# SCH_Dashboy_camera_NiMH_2023-03-29.net
KiCad netlist of a schematic drawn in EasyEDA
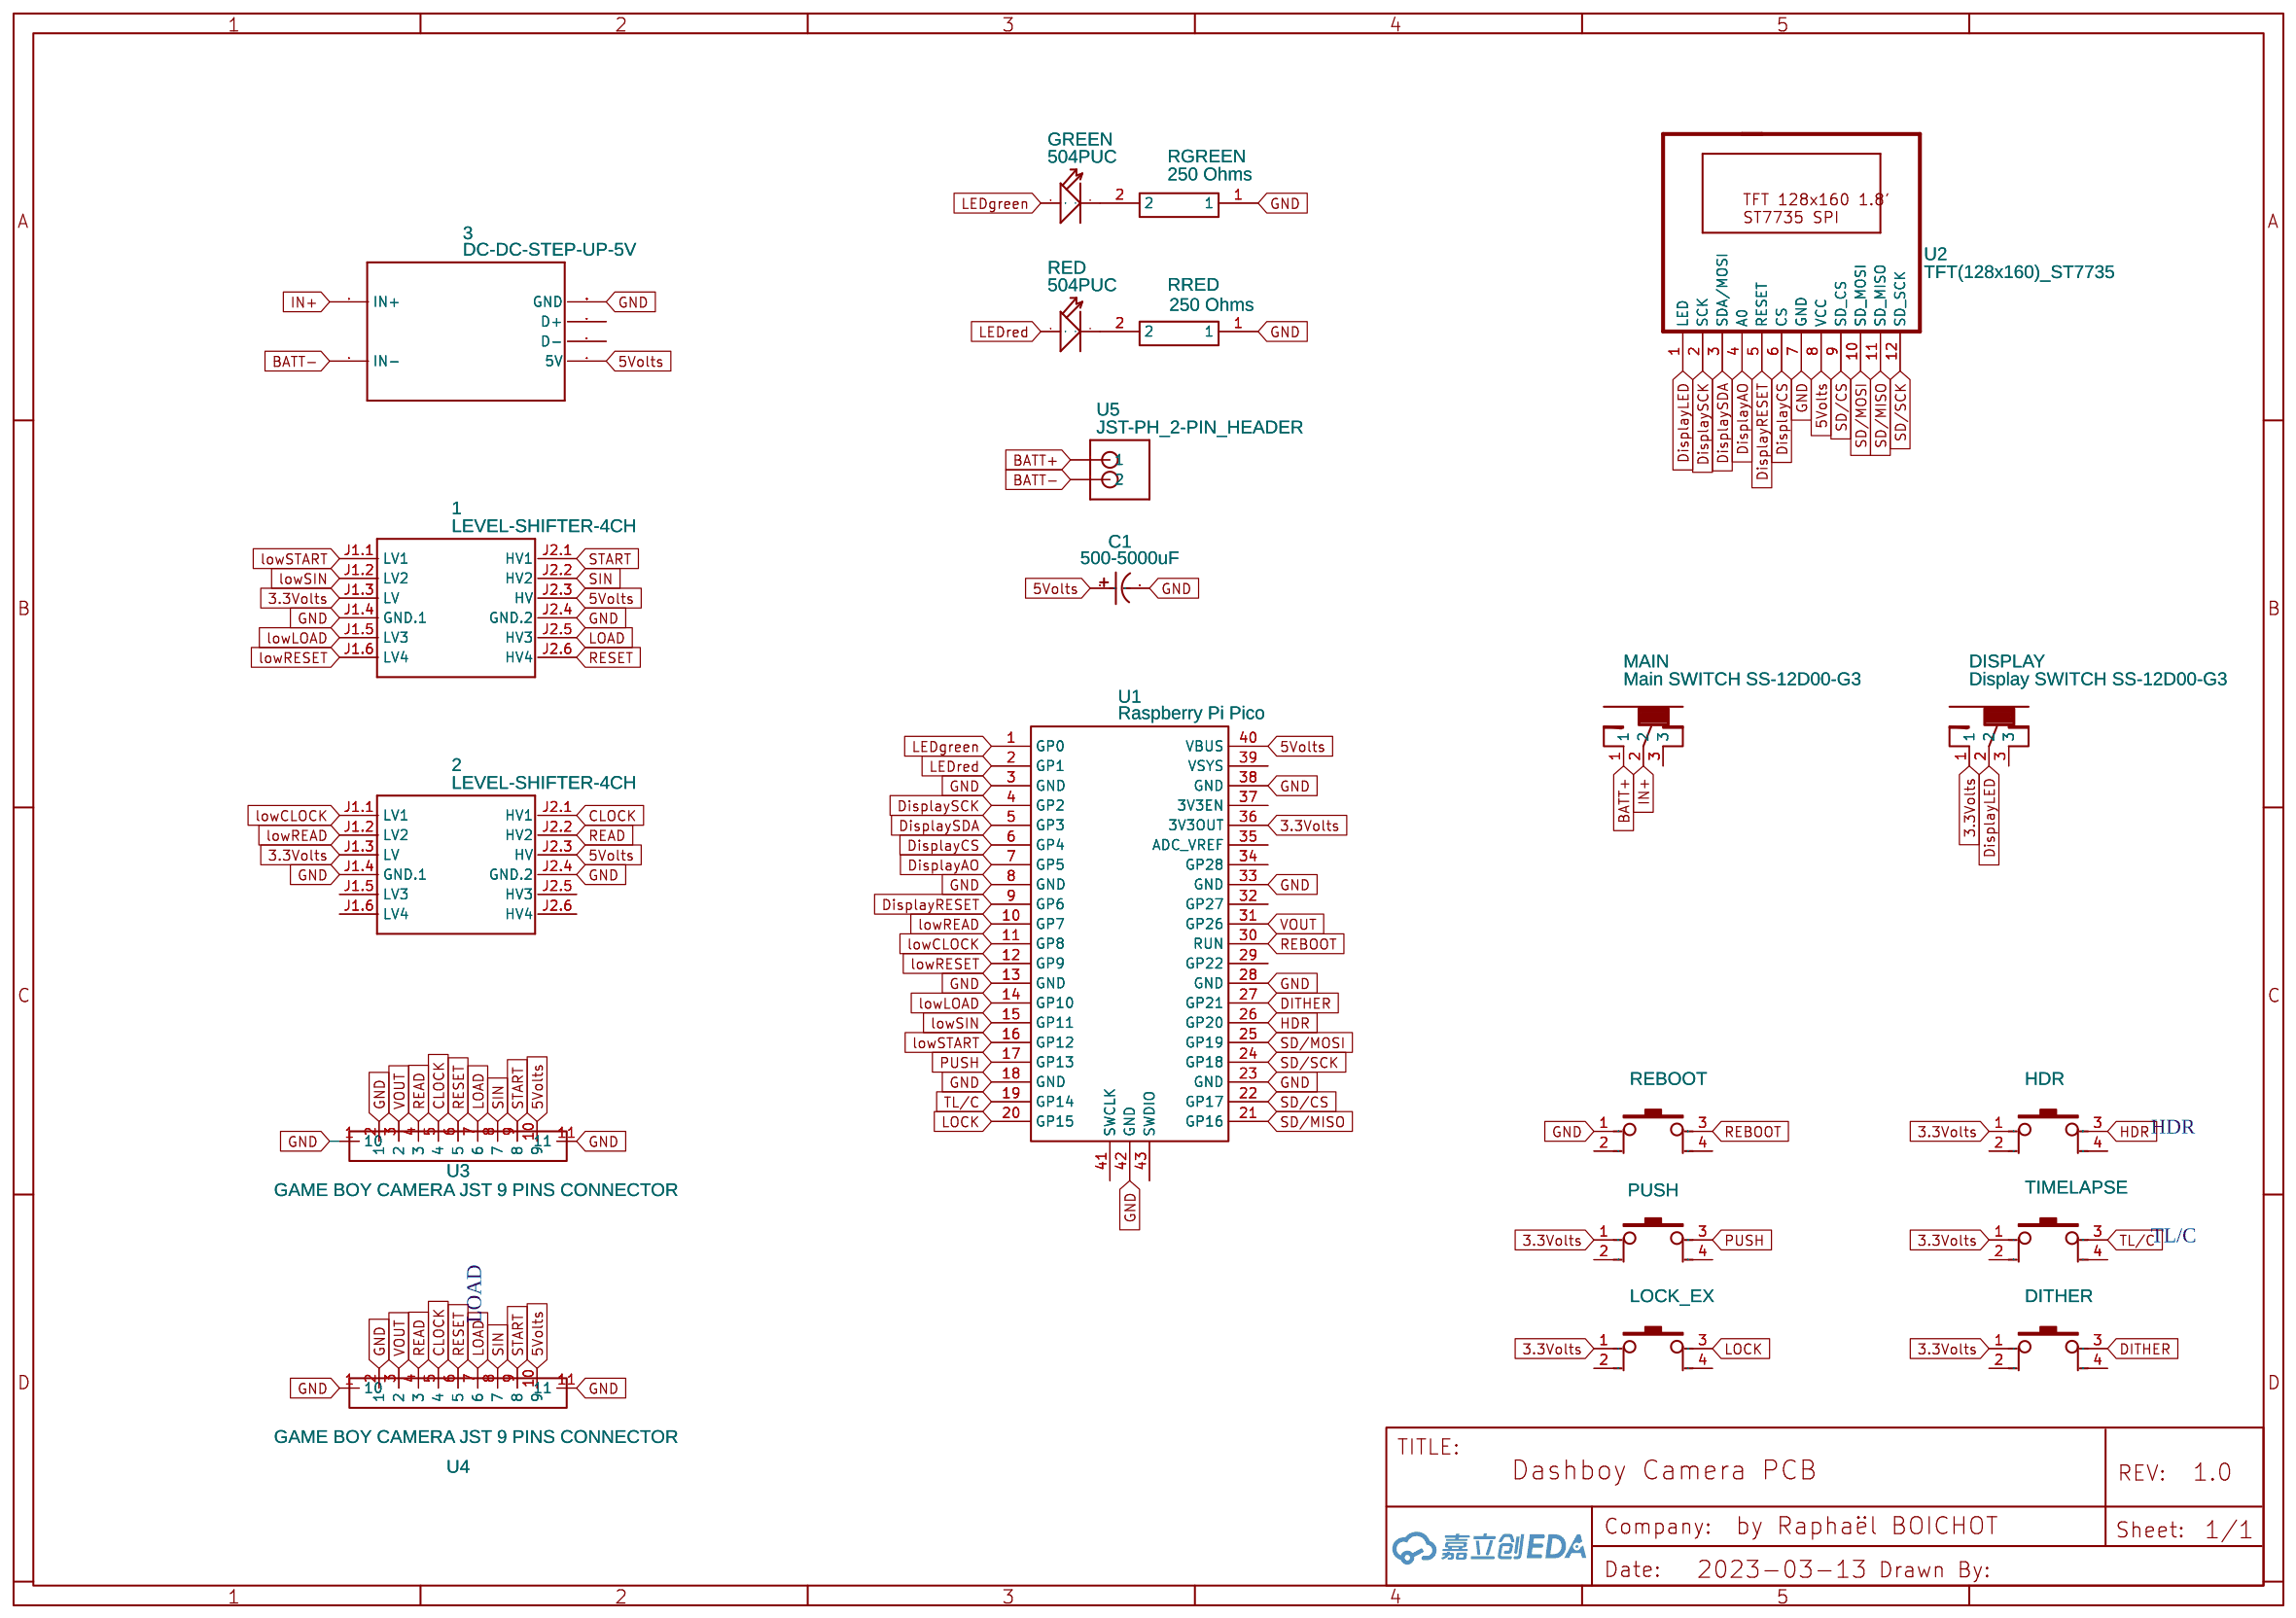
[diagram p0: schematic sheet]

(export (version "E")
  (design (tool "Eeschema 10.0.6"))
  (components
    (comp (ref "1") (value "LEVEL-SHIFTER-4CH") (libsource (lib "") (part "LEVEL-SHIFTER-4CH")))
    (comp (ref "2") (value "LEVEL-SHIFTER-4CH") (libsource (lib "") (part "LEVEL-SHIFTER-4CH")))
    (comp (ref "3") (value "DC-DC-STEP-UP-5V") (libsource (lib "") (part "DC-DC-STEP-UP-5V")))
    (comp (ref "C1")
      (value "500-5000uF")
      (fields
        (field (name "BOM_Manufacturer Part") "GR106M050D11RR0VK2FP0")
        (field (name "BOM_Supplier Part") "C78759")
      )
      (libsource (lib "") (part "electrolytic capacitor 10UF 50V high frequency"))
    )
    (comp (ref "DISPLAY")
      (value "Display SWITCH SS-12D00-G3")
      (fields (field (name "BOM_Manufacturer Part") "TOGGLE SWITCH SS-12D00-G3"))
      (libsource (lib "") (part "TOGGLE SWITCH SS-12D00-G3"))
    )
    (comp (ref "DITHER")
      (value "BoutonPoussoir")
      (fields
        (field (name "BOM_Manufacturer Part") "button6*6*8")
        (field (name "BOM_Supplier Part") "C59982")
      )
      (libsource (lib "") (part "BoutonPoussoir_1"))
    )
    (comp (ref "GREEN") (value "504PUC") (libsource (lib "") (part "504PUC")))
    (comp (ref "HDR")
      (value "BoutonPoussoir")
      (fields
        (field (name "BOM_Manufacturer Part") "button6*6*8")
        (field (name "BOM_Supplier Part") "C59982")
      )
      (libsource (lib "") (part "BoutonPoussoir_2"))
    )
    (comp (ref "LOCK_EX")
      (value "BoutonPoussoir")
      (fields
        (field (name "BOM_Manufacturer Part") "button6*6*8")
        (field (name "BOM_Supplier Part") "C59982")
      )
      (libsource (lib "") (part "BoutonPoussoir_5"))
    )
    (comp (ref "MAIN")
      (value "Main SWITCH SS-12D00-G3")
      (fields (field (name "BOM_Manufacturer Part") "TOGGLE SWITCH SS-12D00-G3"))
      (libsource (lib "") (part "TOGGLE SWITCH SS-12D00-G3_1"))
    )
    (comp (ref "PUSH")
      (value "BoutonPoussoir")
      (fields
        (field (name "BOM_Manufacturer Part") "button6*6*8")
        (field (name "BOM_Supplier Part") "C59982")
      )
      (libsource (lib "") (part "BoutonPoussoir_4"))
    )
    (comp (ref "REBOOT")
      (value "BoutonPoussoir")
      (fields
        (field (name "BOM_Manufacturer Part") "button6*6*8")
        (field (name "BOM_Supplier Part") "C59982")
      )
      (libsource (lib "") (part "BoutonPoussoir"))
    )
    (comp (ref "RED") (value "504PUC") (libsource (lib "") (part "504PUC_1")))
    (comp (ref "RGREEN") (value "250 Ohms") (libsource (lib "") (part "RESITOR")))
    (comp (ref "RRED") (value "250 Ohms") (libsource (lib "") (part "RESITOR_1")))
    (comp (ref "TIMELAPSE")
      (value "BoutonPoussoir")
      (fields
        (field (name "BOM_Manufacturer Part") "button6*6*8")
        (field (name "BOM_Supplier Part") "C59982")
      )
      (libsource (lib "") (part "BoutonPoussoir_3"))
    )
    (comp (ref "U1") (value "Raspberry Pi Pico") (libsource (lib "") (part "Raspberry Pi Pico")))
    (comp (ref "U2") (value "TFT(128x160)_ST7735") (libsource (lib "") (part "TFT(128x160)_ST7735")))
    (comp (ref "U3")
      (value "GAME BOY CAMERA JST 9 PINS CONNECTOR")
      (libsource (lib "") (part "GAME BOY CAMERA JST 9 PINS CONNECTOR"))
    )
    (comp (ref "U4")
      (value "GAME BOY CAMERA JST 9 PINS CONNECTOR")
      (libsource (lib "") (part "GAME BOY CAMERA JST 9 PINS CONNECTOR"))
    )
    (comp (ref "U5") (value "JST-PH_2-PIN_HEADER") (libsource (lib "") (part "JST-PH_2-PIN_HEADER")))
  )
  (nets
    (net (code "1") (name "3.3Volts") (class "Default")
      (node (ref "1") (pin "J1.3") (pinfunction "LV_J1.3") (pintype "bidirectional"))
      (node (ref "2") (pin "J1.3") (pinfunction "LV_J1.3") (pintype "bidirectional"))
      (node (ref "DISPLAY") (pin "1") (pinfunction "1_1") (pintype "bidirectional"))
      (node (ref "DITHER") (pin "1") (pinfunction "1_1") (pintype "input"))
      (node (ref "HDR") (pin "1") (pinfunction "1_1") (pintype "input"))
      (node (ref "LOCK_EX") (pin "1") (pinfunction "1_1") (pintype "input"))
      (node (ref "PUSH") (pin "1") (pinfunction "1_1") (pintype "input"))
      (node (ref "TIMELAPSE") (pin "1") (pinfunction "1_1") (pintype "input"))
      (node (ref "U1") (pin "36") (pinfunction "3V3OUT_36") (pintype "unspecified"))
    )
    (net (code "2") (name "5Volts") (class "Default")
      (node (ref "1") (pin "J2.3") (pinfunction "HV_J2.3") (pintype "bidirectional"))
      (node (ref "2") (pin "J2.3") (pinfunction "HV_J2.3") (pintype "bidirectional"))
      (node (ref "3") (pin "5V") (pinfunction "5V_5V") (pintype "bidirectional"))
      (node (ref "C1") (pin "1") (pinfunction "1_1") (pintype "input"))
      (node (ref "U1") (pin "40") (pinfunction "VBUS_40") (pintype "unspecified"))
      (node (ref "U2") (pin "8") (pinfunction "VCC_8") (pintype "input"))
      (node (ref "U3") (pin "10") (pinfunction "9_10") (pintype "unspecified"))
      (node (ref "U4") (pin "10") (pinfunction "9_10") (pintype "unspecified"))
    )
    (net (code "3") (name "BATT+") (class "Default")
      (node (ref "MAIN") (pin "1") (pinfunction "1_1") (pintype "bidirectional"))
      (node (ref "U5") (pin "P1") (pinfunction "1_P1") (pintype "unspecified"))
    )
    (net (code "4") (name "BATT-") (class "Default")
      (node (ref "3") (pin "IN-") (pinfunction "IN-_IN-") (pintype "bidirectional"))
      (node (ref "U5") (pin "P2") (pinfunction "2_P2") (pintype "unspecified"))
    )
    (net (code "5") (name "CLOCK") (class "Default")
      (node (ref "2") (pin "J2.1") (pinfunction "HV1_J2.1") (pintype "bidirectional"))
      (node (ref "U3") (pin "5") (pinfunction "4_5") (pintype "unspecified"))
      (node (ref "U4") (pin "5") (pinfunction "4_5") (pintype "unspecified"))
    )
    (net (code "6") (name "DITHER") (class "Default")
      (node (ref "DITHER") (pin "3") (pinfunction "3_3") (pintype "input"))
      (node (ref "U1") (pin "27") (pinfunction "GP21_27") (pintype "unspecified"))
    )
    (net (code "7") (name "DisplayAO") (class "Default")
      (node (ref "U1") (pin "7") (pinfunction "GP5_7") (pintype "unspecified"))
      (node (ref "U2") (pin "4") (pinfunction "A0_4") (pintype "input"))
    )
    (net (code "8") (name "DisplayCS") (class "Default")
      (node (ref "U1") (pin "6") (pinfunction "GP4_6") (pintype "unspecified"))
      (node (ref "U2") (pin "6") (pinfunction "CS_6") (pintype "input"))
    )
    (net (code "9") (name "DisplayLED") (class "Default")
      (node (ref "DISPLAY") (pin "2") (pinfunction "2_2") (pintype "bidirectional"))
      (node (ref "U2") (pin "1") (pinfunction "LED_1") (pintype "passive"))
    )
    (net (code "10") (name "DisplayRESET") (class "Default")
      (node (ref "U1") (pin "9") (pinfunction "GP6_9") (pintype "unspecified"))
      (node (ref "U2") (pin "5") (pinfunction "RESET_5") (pintype "input"))
    )
    (net (code "11") (name "DisplaySCK") (class "Default")
      (node (ref "U1") (pin "4") (pinfunction "GP2_4") (pintype "unspecified"))
      (node (ref "U2") (pin "2") (pinfunction "SCK_2") (pintype "output"))
    )
    (net (code "12") (name "DisplaySDA") (class "Default")
      (node (ref "U1") (pin "5") (pinfunction "GP3_5") (pintype "unspecified"))
      (node (ref "U2") (pin "3") (pinfunction "SDA/MOSI_3") (pintype "input"))
    )
    (net (code "13") (name "GND") (class "Default")
      (node (ref "1") (pin "J1.4") (pinfunction "GND.1_J1.4") (pintype "bidirectional"))
      (node (ref "1") (pin "J2.4") (pinfunction "GND.2_J2.4") (pintype "bidirectional"))
      (node (ref "2") (pin "J1.4") (pinfunction "GND.1_J1.4") (pintype "bidirectional"))
      (node (ref "2") (pin "J2.4") (pinfunction "GND.2_J2.4") (pintype "bidirectional"))
      (node (ref "3") (pin "GND") (pinfunction "GND_GND") (pintype "bidirectional"))
      (node (ref "C1") (pin "2") (pinfunction "2_2") (pintype "input"))
      (node (ref "REBOOT") (pin "1") (pinfunction "1_1") (pintype "input"))
      (node (ref "RGREEN") (pin "1") (pinfunction "1_1") (pintype "unspecified"))
      (node (ref "RRED") (pin "1") (pinfunction "1_1") (pintype "unspecified"))
      (node (ref "U1") (pin "13") (pinfunction "GND_13") (pintype "unspecified"))
      (node (ref "U1") (pin "18") (pinfunction "GND_18") (pintype "unspecified"))
      (node (ref "U1") (pin "23") (pinfunction "GND_23") (pintype "unspecified"))
      (node (ref "U1") (pin "28") (pinfunction "GND_28") (pintype "unspecified"))
      (node (ref "U1") (pin "3") (pinfunction "GND_3") (pintype "unspecified"))
      (node (ref "U1") (pin "33") (pinfunction "GND_33") (pintype "unspecified"))
      (node (ref "U1") (pin "38") (pinfunction "GND_38") (pintype "unspecified"))
      (node (ref "U1") (pin "42") (pinfunction "GND_42") (pintype "unspecified"))
      (node (ref "U1") (pin "8") (pinfunction "GND_8") (pintype "unspecified"))
      (node (ref "U2") (pin "7") (pinfunction "GND_7") (pintype "unspecified"))
      (node (ref "U3") (pin "1") (pinfunction "10_1") (pintype "unspecified"))
      (node (ref "U3") (pin "11") (pinfunction "11_11") (pintype "unspecified"))
      (node (ref "U3") (pin "2") (pinfunction "1_2") (pintype "unspecified"))
      (node (ref "U4") (pin "1") (pinfunction "10_1") (pintype "unspecified"))
      (node (ref "U4") (pin "11") (pinfunction "11_11") (pintype "unspecified"))
      (node (ref "U4") (pin "2") (pinfunction "1_2") (pintype "unspecified"))
    )
    (net (code "14") (name "HDR") (class "Default")
      (node (ref "HDR") (pin "3") (pinfunction "3_3") (pintype "input"))
      (node (ref "U1") (pin "26") (pinfunction "GP20_26") (pintype "unspecified"))
    )
    (net (code "15") (name "IN+") (class "Default")
      (node (ref "3") (pin "IN+") (pinfunction "IN+_IN+") (pintype "bidirectional"))
      (node (ref "MAIN") (pin "2") (pinfunction "2_2") (pintype "bidirectional"))
    )
    (net (code "16") (name "LEDgreen") (class "Default")
      (node (ref "GREEN") (pin "+") (pinfunction "+_+") (pintype "unspecified"))
      (node (ref "U1") (pin "1") (pinfunction "GP0_1") (pintype "unspecified"))
    )
    (net (code "17") (name "LEDred") (class "Default")
      (node (ref "RED") (pin "+") (pinfunction "+_+") (pintype "unspecified"))
      (node (ref "U1") (pin "2") (pinfunction "GP1_2") (pintype "unspecified"))
    )
    (net (code "18") (name "LOAD") (class "Default")
      (node (ref "1") (pin "J2.5") (pinfunction "HV3_J2.5") (pintype "bidirectional"))
      (node (ref "U3") (pin "7") (pinfunction "6_7") (pintype "unspecified"))
      (node (ref "U4") (pin "7") (pinfunction "6_7") (pintype "unspecified"))
    )
    (net (code "19") (name "LOCK") (class "Default")
      (node (ref "LOCK_EX") (pin "3") (pinfunction "3_3") (pintype "input"))
      (node (ref "U1") (pin "20") (pinfunction "GP15_20") (pintype "unspecified"))
    )
    (net (code "20") (name "Net-(GREEN-Pad-)") (class "Default")
      (node (ref "GREEN") (pin "-") (pinfunction "-_-") (pintype "unspecified"))
      (node (ref "RGREEN") (pin "2") (pinfunction "2_2") (pintype "unspecified"))
    )
    (net (code "21") (name "Net-(RED-Pad-)") (class "Default")
      (node (ref "RED") (pin "-") (pinfunction "-_-") (pintype "unspecified"))
      (node (ref "RRED") (pin "2") (pinfunction "2_2") (pintype "unspecified"))
    )
    (net (code "22") (name "PUSH") (class "Default")
      (node (ref "PUSH") (pin "3") (pinfunction "3_3") (pintype "input"))
      (node (ref "U1") (pin "17") (pinfunction "GP13_17") (pintype "unspecified"))
    )
    (net (code "23") (name "READ") (class "Default")
      (node (ref "2") (pin "J2.2") (pinfunction "HV2_J2.2") (pintype "bidirectional"))
      (node (ref "U3") (pin "4") (pinfunction "3_4") (pintype "unspecified"))
      (node (ref "U4") (pin "4") (pinfunction "3_4") (pintype "unspecified"))
    )
    (net (code "24") (name "REBOOT") (class "Default")
      (node (ref "REBOOT") (pin "3") (pinfunction "3_3") (pintype "input"))
      (node (ref "U1") (pin "30") (pinfunction "RUN_30") (pintype "unspecified"))
    )
    (net (code "25") (name "RESET") (class "Default")
      (node (ref "1") (pin "J2.6") (pinfunction "HV4_J2.6") (pintype "bidirectional"))
      (node (ref "U3") (pin "6") (pinfunction "5_6") (pintype "unspecified"))
      (node (ref "U4") (pin "6") (pinfunction "5_6") (pintype "unspecified"))
    )
    (net (code "26") (name "SD{slash}CS") (class "Default")
      (node (ref "U1") (pin "22") (pinfunction "GP17_22") (pintype "unspecified"))
      (node (ref "U2") (pin "9") (pinfunction "SD_CS_9") (pintype "input"))
    )
    (net (code "27") (name "SD{slash}MISO") (class "Default")
      (node (ref "U1") (pin "21") (pinfunction "GP16_21") (pintype "unspecified"))
      (node (ref "U2") (pin "11") (pinfunction "SD_MISO_11") (pintype "input"))
    )
    (net (code "28") (name "SD{slash}MOSI") (class "Default")
      (node (ref "U1") (pin "25") (pinfunction "GP19_25") (pintype "unspecified"))
      (node (ref "U2") (pin "10") (pinfunction "SD_MOSI_10") (pintype "input"))
    )
    (net (code "29") (name "SD{slash}SCK") (class "Default")
      (node (ref "U1") (pin "24") (pinfunction "GP18_24") (pintype "unspecified"))
      (node (ref "U2") (pin "12") (pinfunction "SD_SCK_12") (pintype "input"))
    )
    (net (code "30") (name "SIN") (class "Default")
      (node (ref "1") (pin "J2.2") (pinfunction "HV2_J2.2") (pintype "bidirectional"))
      (node (ref "U3") (pin "8") (pinfunction "7_8") (pintype "unspecified"))
      (node (ref "U4") (pin "8") (pinfunction "7_8") (pintype "unspecified"))
    )
    (net (code "31") (name "START") (class "Default")
      (node (ref "1") (pin "J2.1") (pinfunction "HV1_J2.1") (pintype "bidirectional"))
      (node (ref "U3") (pin "9") (pinfunction "8_9") (pintype "unspecified"))
      (node (ref "U4") (pin "9") (pinfunction "8_9") (pintype "unspecified"))
    )
    (net (code "32") (name "TL{slash}C") (class "Default")
      (node (ref "TIMELAPSE") (pin "3") (pinfunction "3_3") (pintype "input"))
      (node (ref "U1") (pin "19") (pinfunction "GP14_19") (pintype "unspecified"))
    )
    (net (code "33") (name "VOUT") (class "Default")
      (node (ref "U1") (pin "31") (pinfunction "GP26_31") (pintype "unspecified"))
      (node (ref "U3") (pin "3") (pinfunction "2_3") (pintype "unspecified"))
      (node (ref "U4") (pin "3") (pinfunction "2_3") (pintype "unspecified"))
    )
    (net (code "34") (name "lowCLOCK") (class "Default")
      (node (ref "2") (pin "J1.1") (pinfunction "LV1_J1.1") (pintype "bidirectional"))
      (node (ref "U1") (pin "11") (pinfunction "GP8_11") (pintype "unspecified"))
    )
    (net (code "35") (name "lowLOAD") (class "Default")
      (node (ref "1") (pin "J1.5") (pinfunction "LV3_J1.5") (pintype "bidirectional"))
      (node (ref "U1") (pin "14") (pinfunction "GP10_14") (pintype "unspecified"))
    )
    (net (code "36") (name "lowREAD") (class "Default")
      (node (ref "2") (pin "J1.2") (pinfunction "LV2_J1.2") (pintype "bidirectional"))
      (node (ref "U1") (pin "10") (pinfunction "GP7_10") (pintype "unspecified"))
    )
    (net (code "37") (name "lowRESET") (class "Default")
      (node (ref "1") (pin "J1.6") (pinfunction "LV4_J1.6") (pintype "bidirectional"))
      (node (ref "U1") (pin "12") (pinfunction "GP9_12") (pintype "unspecified"))
    )
    (net (code "38") (name "lowSIN") (class "Default")
      (node (ref "1") (pin "J1.2") (pinfunction "LV2_J1.2") (pintype "bidirectional"))
      (node (ref "U1") (pin "15") (pinfunction "GP11_15") (pintype "unspecified"))
    )
    (net (code "39") (name "lowSTART") (class "Default")
      (node (ref "1") (pin "J1.1") (pinfunction "LV1_J1.1") (pintype "bidirectional"))
      (node (ref "U1") (pin "16") (pinfunction "GP12_16") (pintype "unspecified"))
    )
    (net (code "40") (name "unconnected-(2-HV3-PadJ2.5)") (class "Default")
      (node (ref "2") (pin "J2.5") (pinfunction "HV3_J2.5") (pintype "bidirectional"))
    )
    (net (code "41") (name "unconnected-(2-HV4-PadJ2.6)") (class "Default")
      (node (ref "2") (pin "J2.6") (pinfunction "HV4_J2.6") (pintype "bidirectional"))
    )
    (net (code "42") (name "unconnected-(2-LV3-PadJ1.5)") (class "Default")
      (node (ref "2") (pin "J1.5") (pinfunction "LV3_J1.5") (pintype "bidirectional"))
    )
    (net (code "43") (name "unconnected-(2-LV4-PadJ1.6)") (class "Default")
      (node (ref "2") (pin "J1.6") (pinfunction "LV4_J1.6") (pintype "bidirectional"))
    )
    (net (code "44") (name "unconnected-(3-PadD+)") (class "Default")
      (node (ref "3") (pin "D+") (pinfunction "D+_D+") (pintype "bidirectional"))
    )
    (net (code "45") (name "unconnected-(3-PadD-)") (class "Default")
      (node (ref "3") (pin "D-") (pinfunction "D-_D-") (pintype "bidirectional"))
    )
    (net (code "46") (name "unconnected-(DISPLAY-Pad3)") (class "Default")
      (node (ref "DISPLAY") (pin "3") (pinfunction "3_3") (pintype "unspecified"))
    )
    (net (code "47") (name "unconnected-(DITHER-Pad2)") (class "Default")
      (node (ref "DITHER") (pin "2") (pinfunction "2_2") (pintype "input"))
    )
    (net (code "48") (name "unconnected-(DITHER-Pad4)") (class "Default")
      (node (ref "DITHER") (pin "4") (pinfunction "4_4") (pintype "input"))
    )
    (net (code "49") (name "unconnected-(HDR-Pad2)") (class "Default")
      (node (ref "HDR") (pin "2") (pinfunction "2_2") (pintype "input"))
    )
    (net (code "50") (name "unconnected-(HDR-Pad4)") (class "Default")
      (node (ref "HDR") (pin "4") (pinfunction "4_4") (pintype "input"))
    )
    (net (code "51") (name "unconnected-(LOCK_EX-Pad2)") (class "Default")
      (node (ref "LOCK_EX") (pin "2") (pinfunction "2_2") (pintype "input"))
    )
    (net (code "52") (name "unconnected-(LOCK_EX-Pad4)") (class "Default")
      (node (ref "LOCK_EX") (pin "4") (pinfunction "4_4") (pintype "input"))
    )
    (net (code "53") (name "unconnected-(MAIN-Pad3)") (class "Default")
      (node (ref "MAIN") (pin "3") (pinfunction "3_3") (pintype "unspecified"))
    )
    (net (code "54") (name "unconnected-(PUSH-Pad2)") (class "Default")
      (node (ref "PUSH") (pin "2") (pinfunction "2_2") (pintype "input"))
    )
    (net (code "55") (name "unconnected-(PUSH-Pad4)") (class "Default")
      (node (ref "PUSH") (pin "4") (pinfunction "4_4") (pintype "input"))
    )
    (net (code "56") (name "unconnected-(REBOOT-Pad2)") (class "Default")
      (node (ref "REBOOT") (pin "2") (pinfunction "2_2") (pintype "input"))
    )
    (net (code "57") (name "unconnected-(REBOOT-Pad4)") (class "Default")
      (node (ref "REBOOT") (pin "4") (pinfunction "4_4") (pintype "input"))
    )
    (net (code "58") (name "unconnected-(TIMELAPSE-Pad2)") (class "Default")
      (node (ref "TIMELAPSE") (pin "2") (pinfunction "2_2") (pintype "input"))
    )
    (net (code "59") (name "unconnected-(TIMELAPSE-Pad4)") (class "Default")
      (node (ref "TIMELAPSE") (pin "4") (pinfunction "4_4") (pintype "input"))
    )
    (net (code "60") (name "unconnected-(U1-3V3EN-Pad37)") (class "Default")
      (node (ref "U1") (pin "37") (pinfunction "3V3EN_37") (pintype "unspecified"))
    )
    (net (code "61") (name "unconnected-(U1-ADC_VREF-Pad35)") (class "Default")
      (node (ref "U1") (pin "35") (pinfunction "ADC_VREF_35") (pintype "unspecified"))
    )
    (net (code "62") (name "unconnected-(U1-GP22-Pad29)") (class "Default")
      (node (ref "U1") (pin "29") (pinfunction "GP22_29") (pintype "unspecified"))
    )
    (net (code "63") (name "unconnected-(U1-GP27-Pad32)") (class "Default")
      (node (ref "U1") (pin "32") (pinfunction "GP27_32") (pintype "unspecified"))
    )
    (net (code "64") (name "unconnected-(U1-GP28-Pad34)") (class "Default")
      (node (ref "U1") (pin "34") (pinfunction "GP28_34") (pintype "unspecified"))
    )
    (net (code "65") (name "unconnected-(U1-SWCLK-Pad41)") (class "Default")
      (node (ref "U1") (pin "41") (pinfunction "SWCLK_41") (pintype "unspecified"))
    )
    (net (code "66") (name "unconnected-(U1-SWDIO-Pad43)") (class "Default")
      (node (ref "U1") (pin "43") (pinfunction "SWDIO_43") (pintype "unspecified"))
    )
    (net (code "67") (name "unconnected-(U1-VSYS-Pad39)") (class "Default")
      (node (ref "U1") (pin "39") (pinfunction "VSYS_39") (pintype "unspecified"))
    )
  )
)
